# STLINKV3_Adapter.net
KiCad netlist of a schematic drawn in Altium Designer
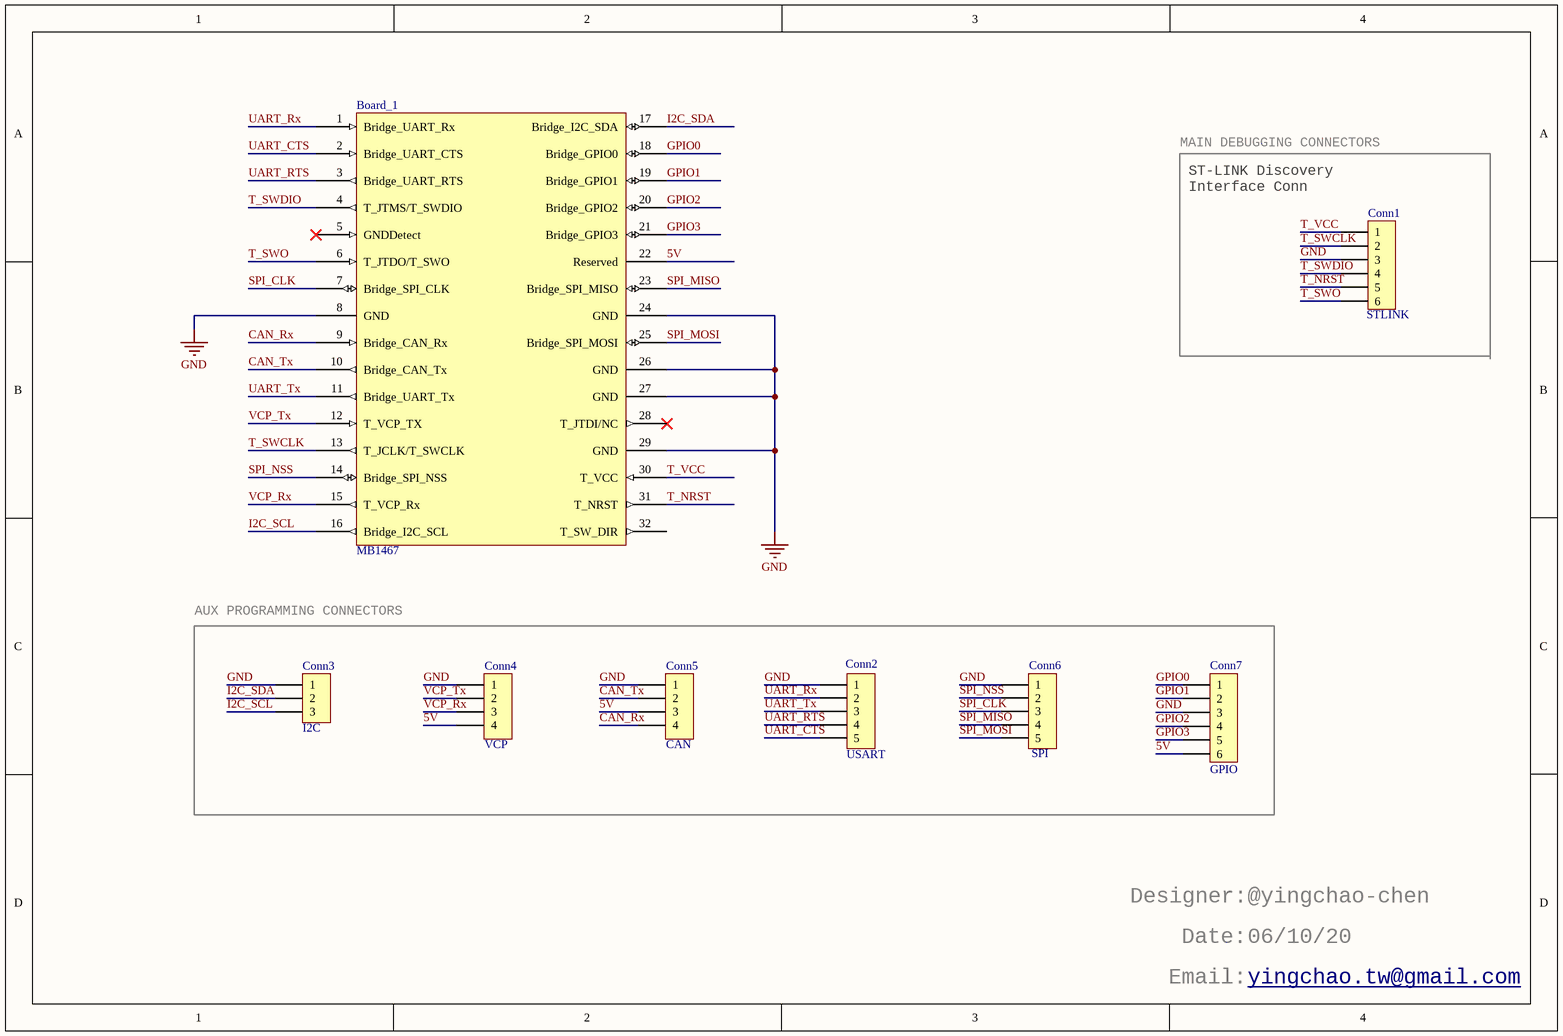
[diagram p0: STLINKV3_Adapter.SchDoc]

(export (version "E")
  (design (tool "Eeschema 10.0.6"))
  (components
    (comp (ref "Board_1")
      (value "MB1467")
      (footprint "MB1467")
      (libsource (lib "Integrated_Library1") (part "MB1467"))
    )
    (comp (ref "Conn1")
      (value "STLINK")
      (footprint "CONNECT_6P_90")
      (description "Header, 6-Pin")
      (libsource (lib "Integrated_Library1") (part "CONN_06"))
    )
    (comp (ref "Conn2")
      (value "USART")
      (footprint "CONNECT_5P")
      (description "Header, 5-Pin")
      (libsource (lib "Integrated_Library1") (part "CONN_05"))
    )
    (comp (ref "Conn3")
      (value "I2C")
      (footprint "CONNECT_3P")
      (description "Header, 3-Pin")
      (libsource (lib "Integrated_Library1") (part "CONN_03"))
    )
    (comp (ref "Conn4")
      (value "VCP")
      (footprint "CONNECT_4P")
      (description "Header, 4-Pin")
      (libsource (lib "Integrated_Library1") (part "CONN_04"))
    )
    (comp (ref "Conn5")
      (value "CAN")
      (footprint "CONNECT_4P")
      (description "Header, 4-Pin")
      (libsource (lib "Integrated_Library1") (part "CONN_04"))
    )
    (comp (ref "Conn6")
      (value "SPI")
      (footprint "CONNECT_5P")
      (description "Header, 5-Pin")
      (libsource (lib "Integrated_Library1") (part "CONN_05"))
    )
    (comp (ref "Conn7")
      (value "GPIO")
      (footprint "CONNECT_6P")
      (description "Header, 6-Pin")
      (libsource (lib "Integrated_Library1") (part "CONN_06"))
    )
  )
  (nets
    (net (code "1") (name "/5V") (class "Default")
      (node (ref "Board_1") (pin "22") (pinfunction "Reserved_22") (pintype "passive"))
      (node (ref "Conn4") (pin "4") (pinfunction "4_4") (pintype "passive"))
      (node (ref "Conn5") (pin "3") (pinfunction "3_3") (pintype "passive"))
      (node (ref "Conn7") (pin "6") (pinfunction "6_6") (pintype "passive"))
    )
    (net (code "2") (name "/CAN_Rx") (class "Default")
      (node (ref "Board_1") (pin "9") (pinfunction "Bridge_CAN_Rx_9") (pintype "input"))
      (node (ref "Conn5") (pin "4") (pinfunction "4_4") (pintype "passive"))
    )
    (net (code "3") (name "/CAN_Tx") (class "Default")
      (node (ref "Board_1") (pin "10") (pinfunction "Bridge_CAN_Tx_10") (pintype "output"))
      (node (ref "Conn5") (pin "2") (pinfunction "2_2") (pintype "passive"))
    )
    (net (code "4") (name "/GPIO0") (class "Default")
      (node (ref "Board_1") (pin "18") (pinfunction "Bridge_GPIO0_18") (pintype "bidirectional"))
      (node (ref "Conn7") (pin "1") (pinfunction "1_1") (pintype "passive"))
    )
    (net (code "5") (name "/GPIO1") (class "Default")
      (node (ref "Board_1") (pin "19") (pinfunction "Bridge_GPIO1_19") (pintype "bidirectional"))
      (node (ref "Conn7") (pin "2") (pinfunction "2_2") (pintype "passive"))
    )
    (net (code "6") (name "/GPIO2") (class "Default")
      (node (ref "Board_1") (pin "20") (pinfunction "Bridge_GPIO2_20") (pintype "bidirectional"))
      (node (ref "Conn7") (pin "4") (pinfunction "4_4") (pintype "passive"))
    )
    (net (code "7") (name "/GPIO3") (class "Default")
      (node (ref "Board_1") (pin "21") (pinfunction "Bridge_GPIO3_21") (pintype "bidirectional"))
      (node (ref "Conn7") (pin "5") (pinfunction "5_5") (pintype "passive"))
    )
    (net (code "8") (name "/I2C_SCL") (class "Default")
      (node (ref "Board_1") (pin "16") (pinfunction "Bridge_I2C_SCL_16") (pintype "output"))
      (node (ref "Conn3") (pin "3") (pinfunction "3_3") (pintype "passive"))
    )
    (net (code "9") (name "/I2C_SDA") (class "Default")
      (node (ref "Board_1") (pin "17") (pinfunction "Bridge_I2C_SDA_17") (pintype "bidirectional"))
      (node (ref "Conn3") (pin "2") (pinfunction "2_2") (pintype "passive"))
    )
    (net (code "10") (name "/SPI_CLK") (class "Default")
      (node (ref "Board_1") (pin "7") (pinfunction "Bridge_SPI_CLK_7") (pintype "bidirectional"))
      (node (ref "Conn6") (pin "3") (pinfunction "3_3") (pintype "passive"))
    )
    (net (code "11") (name "/SPI_MISO") (class "Default")
      (node (ref "Board_1") (pin "23") (pinfunction "Bridge_SPI_MISO_23") (pintype "bidirectional"))
      (node (ref "Conn6") (pin "4") (pinfunction "4_4") (pintype "passive"))
    )
    (net (code "12") (name "/SPI_MOSI") (class "Default")
      (node (ref "Board_1") (pin "25") (pinfunction "Bridge_SPI_MOSI_25") (pintype "bidirectional"))
      (node (ref "Conn6") (pin "5") (pinfunction "5_5") (pintype "passive"))
    )
    (net (code "13") (name "/SPI_NSS") (class "Default")
      (node (ref "Board_1") (pin "14") (pinfunction "Bridge_SPI_NSS_14") (pintype "bidirectional"))
      (node (ref "Conn6") (pin "2") (pinfunction "2_2") (pintype "passive"))
    )
    (net (code "14") (name "/T_NRST") (class "Default")
      (node (ref "Board_1") (pin "31") (pinfunction "T_NRST_31") (pintype "output"))
      (node (ref "Conn1") (pin "5") (pinfunction "5_5") (pintype "passive"))
    )
    (net (code "15") (name "/T_SWCLK") (class "Default")
      (node (ref "Board_1") (pin "13") (pinfunction "T_JCLK/T_SWCLK_13") (pintype "output"))
      (node (ref "Conn1") (pin "2") (pinfunction "2_2") (pintype "passive"))
    )
    (net (code "16") (name "/T_SWDIO") (class "Default")
      (node (ref "Board_1") (pin "4") (pinfunction "T_JTMS/T_SWDIO_4") (pintype "output"))
      (node (ref "Conn1") (pin "4") (pinfunction "4_4") (pintype "passive"))
    )
    (net (code "17") (name "/T_SWO") (class "Default")
      (node (ref "Board_1") (pin "6") (pinfunction "T_JTDO/T_SWO_6") (pintype "input"))
      (node (ref "Conn1") (pin "6") (pinfunction "6_6") (pintype "passive"))
    )
    (net (code "18") (name "/T_VCC") (class "Default")
      (node (ref "Board_1") (pin "30") (pinfunction "T_VCC_30") (pintype "input"))
      (node (ref "Conn1") (pin "1") (pinfunction "1_1") (pintype "passive"))
    )
    (net (code "19") (name "/UART_CTS") (class "Default")
      (node (ref "Board_1") (pin "2") (pinfunction "Bridge_UART_CTS_2") (pintype "input"))
      (node (ref "Conn2") (pin "5") (pinfunction "5_5") (pintype "passive"))
    )
    (net (code "20") (name "/UART_RTS") (class "Default")
      (node (ref "Board_1") (pin "3") (pinfunction "Bridge_UART_RTS_3") (pintype "output"))
      (node (ref "Conn2") (pin "4") (pinfunction "4_4") (pintype "passive"))
    )
    (net (code "21") (name "/UART_Rx") (class "Default")
      (node (ref "Board_1") (pin "1") (pinfunction "Bridge_UART_Rx_1") (pintype "input"))
      (node (ref "Conn2") (pin "2") (pinfunction "2_2") (pintype "passive"))
    )
    (net (code "22") (name "/UART_Tx") (class "Default")
      (node (ref "Board_1") (pin "11") (pinfunction "Bridge_UART_Tx_11") (pintype "output"))
      (node (ref "Conn2") (pin "3") (pinfunction "3_3") (pintype "passive"))
    )
    (net (code "23") (name "/VCP_Rx") (class "Default")
      (node (ref "Board_1") (pin "15") (pinfunction "T_VCP_Rx_15") (pintype "output"))
      (node (ref "Conn4") (pin "3") (pinfunction "3_3") (pintype "passive"))
    )
    (net (code "24") (name "/VCP_Tx") (class "Default")
      (node (ref "Board_1") (pin "12") (pinfunction "T_VCP_TX_12") (pintype "input"))
      (node (ref "Conn4") (pin "2") (pinfunction "2_2") (pintype "passive"))
    )
    (net (code "25") (name "GND") (class "Default")
      (node (ref "Board_1") (pin "24") (pinfunction "GND_24") (pintype "passive"))
      (node (ref "Board_1") (pin "26") (pinfunction "GND_26") (pintype "passive"))
      (node (ref "Board_1") (pin "27") (pinfunction "GND_27") (pintype "passive"))
      (node (ref "Board_1") (pin "29") (pinfunction "GND_29") (pintype "passive"))
      (node (ref "Board_1") (pin "8") (pinfunction "GND_8") (pintype "passive"))
      (node (ref "Conn1") (pin "3") (pinfunction "3_3") (pintype "passive"))
      (node (ref "Conn2") (pin "1") (pinfunction "1_1") (pintype "passive"))
      (node (ref "Conn3") (pin "1") (pinfunction "1_1") (pintype "passive"))
      (node (ref "Conn4") (pin "1") (pinfunction "1_1") (pintype "passive"))
      (node (ref "Conn5") (pin "1") (pinfunction "1_1") (pintype "passive"))
      (node (ref "Conn6") (pin "1") (pinfunction "1_1") (pintype "passive"))
      (node (ref "Conn7") (pin "3") (pinfunction "3_3") (pintype "passive"))
    )
    (net (code "26") (name "unconnected-(Board_1-GNDDetect-Pad5)") (class "Default")
      (node (ref "Board_1") (pin "5") (pinfunction "GNDDetect_5") (pintype "input+no_connect"))
    )
    (net (code "27") (name "unconnected-(Board_1-T_JTDI{slash}NC-Pad28)") (class "Default")
      (node (ref "Board_1") (pin "28") (pinfunction "T_JTDI/NC_28") (pintype "output+no_connect"))
    )
    (net (code "28") (name "unconnected-(Board_1-T_SW_DIR-Pad32)") (class "Default")
      (node (ref "Board_1") (pin "32") (pinfunction "T_SW_DIR_32") (pintype "output"))
    )
  )
)
